# KC_BaseBoard4CompareTest-V0_3.net
KiCad netlist of a schematic drawn in Altium Designer
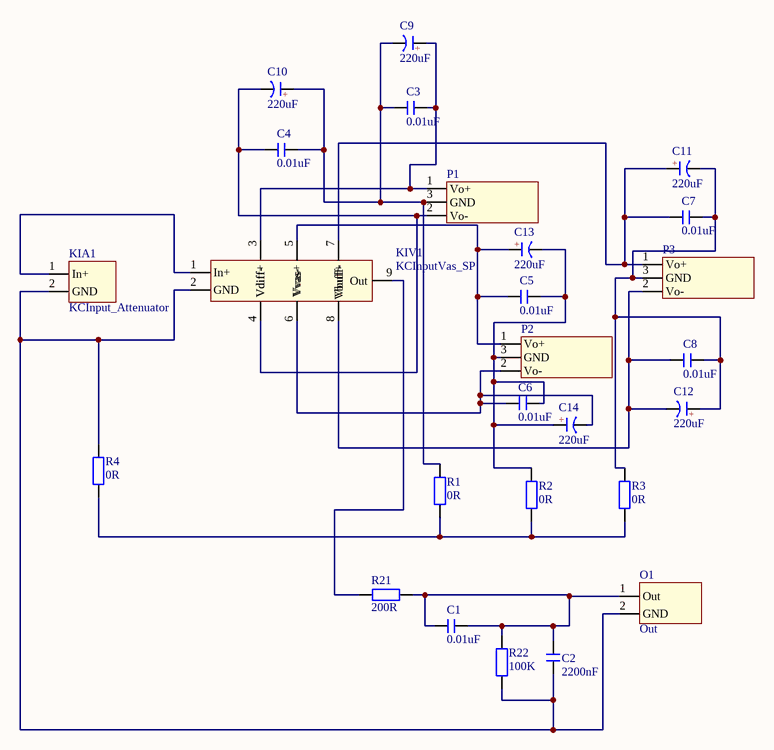
[diagram p0: KC_BaseBoard4CompareTest-V0.3.SchDoc]

(export (version "E")
  (design (tool "Eeschema 10.0.6"))
  (components
    (comp (ref "C1")
      (value "0.01uF")
      (footprint "CBB 6.3*6.3*5")
      (description "CBB电容")
      (fields (field (name "版权归属") "源创客"))
      (libsource (lib "电阻-电容-电感") (part "C-CBB"))
    )
    (comp (ref "C2")
      (value "2200nF")
      (footprint "CBB 6.3*6.3*5")
      (description "CBB电容")
      (fields (field (name "版权归属") "源创客"))
      (libsource (lib "电阻-电容-电感") (part "C-CBB"))
    )
    (comp (ref "C3")
      (value "0.01uF")
      (footprint "CBB 6.3*6.3*5")
      (description "CBB电容")
      (fields (field (name "版权归属") "源创客"))
      (libsource (lib "电阻-电容-电感") (part "C-CBB"))
    )
    (comp (ref "C4")
      (value "0.01uF")
      (footprint "CBB 6.3*6.3*5")
      (description "CBB电容")
      (fields (field (name "版权归属") "源创客"))
      (libsource (lib "电阻-电容-电感") (part "C-CBB"))
    )
    (comp (ref "C5")
      (value "0.01uF")
      (footprint "CBB 6.3*6.3*5")
      (description "CBB电容")
      (fields (field (name "版权归属") "源创客"))
      (libsource (lib "电阻-电容-电感") (part "C-CBB"))
    )
    (comp (ref "C6")
      (value "0.01uF")
      (footprint "CBB 6.3*6.3*5")
      (description "CBB电容")
      (fields (field (name "版权归属") "源创客"))
      (libsource (lib "电阻-电容-电感") (part "C-CBB"))
    )
    (comp (ref "C7")
      (value "0.01uF")
      (footprint "CBB 6.3*6.3*5")
      (description "CBB电容")
      (fields (field (name "版权归属") "源创客"))
      (libsource (lib "电阻-电容-电感") (part "C-CBB"))
    )
    (comp (ref "C8")
      (value "0.01uF")
      (footprint "CBB 6.3*6.3*5")
      (description "CBB电容")
      (fields (field (name "版权归属") "源创客"))
      (libsource (lib "电阻-电容-电感") (part "C-CBB"))
    )
    (comp (ref "C9")
      (value "220uF")
      (footprint "CAP 5.0*10*12.5")
      (description "直插电解电容")
      (fields (field (name "版权归属") "源创客"))
      (libsource (lib "电阻-电容-电感") (part "C-CAP"))
    )
    (comp (ref "C10")
      (value "220uF")
      (footprint "CAP 5.0*10*12.5")
      (description "直插电解电容")
      (fields (field (name "版权归属") "源创客"))
      (libsource (lib "电阻-电容-电感") (part "C-CAP"))
    )
    (comp (ref "C11")
      (value "220uF")
      (footprint "CAP 5.0*10*12.5")
      (description "直插电解电容")
      (fields (field (name "版权归属") "源创客"))
      (libsource (lib "电阻-电容-电感") (part "C-CAP"))
    )
    (comp (ref "C12")
      (value "220uF")
      (footprint "CAP 5.0*10*12.5")
      (description "直插电解电容")
      (fields (field (name "版权归属") "源创客"))
      (libsource (lib "电阻-电容-电感") (part "C-CAP"))
    )
    (comp (ref "C13")
      (value "220uF")
      (footprint "CAP 5.0*10*12.5")
      (description "直插电解电容")
      (fields (field (name "版权归属") "源创客"))
      (libsource (lib "电阻-电容-电感") (part "C-CAP"))
    )
    (comp (ref "C14")
      (value "220uF")
      (footprint "CAP 5.0*10*12.5")
      (description "直插电解电容")
      (fields (field (name "版权归属") "源创客"))
      (libsource (lib "电阻-电容-电感") (part "C-CAP"))
    )
    (comp (ref "KIA1")
      (value "KCInput_Attenuator")
      (footprint "KCIn_Attenuator")
      (description "King Cello Input Attenuator")
      (libsource (lib "KC_amp") (part "KCInput_Attenuator"))
    )
    (comp (ref "KIV1")
      (value "KCInputVas_SP")
      (footprint "KCIn_VAS_SP_M4")
      (description "King Cello Input Stage and VAS for Seperated Power")
      (libsource (lib "KC_amp") (part "KCInputVas_SP"))
    )
    (comp (ref "O1")
      (value "Out")
      (footprint "Signal_Terminal")
      (description "Signal Out")
      (libsource (lib "KC_amp") (part "Signal_Out"))
    )
    (comp (ref "P1")
      (value "Vdiff")
      (footprint "KC_MBPowerReg4Compare")
      (description "King Cello Compare Test Power")
      (libsource (lib "KC_amp") (part "MainBoardPowerRegulator4CompareTest"))
    )
    (comp (ref "P2")
      (value "Vvas")
      (footprint "KC_MBPowerReg4Compare")
      (description "King Cello Compare Test Power")
      (libsource (lib "KC_amp") (part "MainBoardPowerRegulator4CompareTest"))
    )
    (comp (ref "P3")
      (value "Vbuff")
      (footprint "KC_MBPowerReg4Compare")
      (description "King Cello Compare Test Power")
      (libsource (lib "KC_amp") (part "MainBoardPowerRegulator4CompareTest"))
    )
    (comp (ref "R1")
      (value "0R")
      (footprint "RS 1/4W")
      (description "直插色环电阻")
      (fields (field (name "版权归属") "源创客"))
      (libsource (lib "电阻-电容-电感") (part "R-CRR"))
    )
    (comp (ref "R2")
      (value "0R")
      (footprint "RS 1/4W")
      (description "直插色环电阻")
      (fields (field (name "版权归属") "源创客"))
      (libsource (lib "电阻-电容-电感") (part "R-CRR"))
    )
    (comp (ref "R3")
      (value "0R")
      (footprint "RS 1/4W")
      (description "直插色环电阻")
      (fields (field (name "版权归属") "源创客"))
      (libsource (lib "电阻-电容-电感") (part "R-CRR"))
    )
    (comp (ref "R4")
      (value "0R")
      (footprint "RS 1/4W")
      (description "直插色环电阻")
      (fields (field (name "版权归属") "源创客"))
      (libsource (lib "电阻-电容-电感") (part "R-CRR"))
    )
    (comp (ref "R21")
      (value "200R")
      (footprint "RS 1/4W")
      (description "直插色环电阻")
      (fields (field (name "版权归属") "源创客"))
      (libsource (lib "电阻-电容-电感") (part "R-CRR"))
    )
    (comp (ref "R22")
      (value "100K")
      (footprint "RS 1/4W")
      (description "直插色环电阻")
      (fields (field (name "版权归属") "源创客"))
      (libsource (lib "电阻-电容-电感") (part "R-CRR"))
    )
  )
  (nets
    (net (code "1") (name "Net-(C9-A)") (class "Default")
      (node (ref "C3") (pin "2") (pinfunction "2_2") (pintype "passive"))
      (node (ref "C9") (pin "1") (pinfunction "A_1") (pintype "passive"))
      (node (ref "KIV1") (pin "3") (pinfunction "Vdiff+_3") (pintype "passive"))
      (node (ref "P1") (pin "1") (pinfunction "Vo+_1") (pintype "passive"))
    )
    (net (code "2") (name "Net-(C10-A)") (class "Default")
      (node (ref "C10") (pin "1") (pinfunction "A_1") (pintype "passive"))
      (node (ref "C3") (pin "1") (pinfunction "1_1") (pintype "passive"))
      (node (ref "C4") (pin "2") (pinfunction "2_2") (pintype "passive"))
      (node (ref "C9") (pin "2") (pinfunction "K_2") (pintype "passive"))
      (node (ref "P1") (pin "3") (pinfunction "GND_3") (pintype "passive"))
      (node (ref "R1") (pin "2") (pinfunction "2_2") (pintype "passive"))
    )
    (net (code "3") (name "Net-(C10-K)") (class "Default")
      (node (ref "C10") (pin "2") (pinfunction "K_2") (pintype "passive"))
      (node (ref "C4") (pin "1") (pinfunction "1_1") (pintype "passive"))
      (node (ref "KIV1") (pin "4") (pinfunction "Vdiff-_4") (pintype "passive"))
      (node (ref "P1") (pin "2") (pinfunction "Vo-_2") (pintype "passive"))
    )
    (net (code "4") (name "Net-(C11-A)") (class "Default")
      (node (ref "C11") (pin "1") (pinfunction "A_1") (pintype "passive"))
      (node (ref "C7") (pin "1") (pinfunction "1_1") (pintype "passive"))
      (node (ref "KIV1") (pin "7") (pinfunction "Vbuff+_7") (pintype "passive"))
      (node (ref "P3") (pin "1") (pinfunction "Vo+_1") (pintype "passive"))
    )
    (net (code "5") (name "Net-(C11-K)") (class "Default")
      (node (ref "C11") (pin "2") (pinfunction "K_2") (pintype "passive"))
      (node (ref "C12") (pin "1") (pinfunction "A_1") (pintype "passive"))
      (node (ref "C7") (pin "2") (pinfunction "2_2") (pintype "passive"))
      (node (ref "C8") (pin "2") (pinfunction "2_2") (pintype "passive"))
      (node (ref "P3") (pin "3") (pinfunction "GND_3") (pintype "passive"))
      (node (ref "R3") (pin "2") (pinfunction "2_2") (pintype "passive"))
    )
    (net (code "6") (name "Net-(C12-K)") (class "Default")
      (node (ref "C12") (pin "2") (pinfunction "K_2") (pintype "passive"))
      (node (ref "C8") (pin "1") (pinfunction "1_1") (pintype "passive"))
      (node (ref "KIV1") (pin "8") (pinfunction "Vbuff-_8") (pintype "passive"))
      (node (ref "P3") (pin "2") (pinfunction "Vo-_2") (pintype "passive"))
    )
    (net (code "7") (name "Net-(C13-A)") (class "Default")
      (node (ref "C13") (pin "1") (pinfunction "A_1") (pintype "passive"))
      (node (ref "C5") (pin "1") (pinfunction "1_1") (pintype "passive"))
      (node (ref "KIV1") (pin "5") (pinfunction "Vvas+_5") (pintype "passive"))
      (node (ref "P2") (pin "1") (pinfunction "Vo+_1") (pintype "passive"))
    )
    (net (code "8") (name "Net-(C13-K)") (class "Default")
      (node (ref "C13") (pin "2") (pinfunction "K_2") (pintype "passive"))
      (node (ref "C14") (pin "1") (pinfunction "A_1") (pintype "passive"))
      (node (ref "C5") (pin "2") (pinfunction "2_2") (pintype "passive"))
      (node (ref "C6") (pin "2") (pinfunction "2_2") (pintype "passive"))
      (node (ref "P2") (pin "3") (pinfunction "GND_3") (pintype "passive"))
      (node (ref "R2") (pin "2") (pinfunction "2_2") (pintype "passive"))
    )
    (net (code "9") (name "Net-(C14-K)") (class "Default")
      (node (ref "C14") (pin "2") (pinfunction "K_2") (pintype "passive"))
      (node (ref "C6") (pin "1") (pinfunction "1_1") (pintype "passive"))
      (node (ref "KIV1") (pin "6") (pinfunction "Vvas-_6") (pintype "passive"))
      (node (ref "P2") (pin "2") (pinfunction "Vo-_2") (pintype "passive"))
    )
    (net (code "10") (name "Net-(KIA1-GND)") (class "Default")
      (node (ref "C2") (pin "2") (pinfunction "2_2") (pintype "passive"))
      (node (ref "KIA1") (pin "2") (pinfunction "GND_2") (pintype "passive"))
      (node (ref "KIV1") (pin "2") (pinfunction "GND_2") (pintype "passive"))
      (node (ref "O1") (pin "2") (pinfunction "GND_2") (pintype "passive"))
      (node (ref "R22") (pin "2") (pinfunction "2_2") (pintype "passive"))
      (node (ref "R4") (pin "2") (pinfunction "2_2") (pintype "passive"))
    )
    (net (code "11") (name "Net-(KIA1-In+)") (class "Default")
      (node (ref "KIA1") (pin "1") (pinfunction "In+_1") (pintype "passive"))
      (node (ref "KIV1") (pin "1") (pinfunction "In+_1") (pintype "passive"))
    )
    (net (code "12") (name "Net-(KIV1-Out)") (class "Default")
      (node (ref "KIV1") (pin "9") (pinfunction "Out_9") (pintype "passive"))
      (node (ref "R21") (pin "2") (pinfunction "2_2") (pintype "passive"))
    )
    (net (code "13") (name "Net-(O1-Out)") (class "Default")
      (node (ref "C1") (pin "1") (pinfunction "1_1") (pintype "passive"))
      (node (ref "C1") (pin "2") (pinfunction "2_2") (pintype "passive"))
      (node (ref "C2") (pin "1") (pinfunction "1_1") (pintype "passive"))
      (node (ref "O1") (pin "1") (pinfunction "Out_1") (pintype "passive"))
      (node (ref "R21") (pin "1") (pinfunction "1_1") (pintype "passive"))
      (node (ref "R22") (pin "1") (pinfunction "1_1") (pintype "passive"))
    )
    (net (code "14") (name "Net-(R1-Pad1)") (class "Default")
      (node (ref "R1") (pin "1") (pinfunction "1_1") (pintype "passive"))
      (node (ref "R2") (pin "1") (pinfunction "1_1") (pintype "passive"))
      (node (ref "R3") (pin "1") (pinfunction "1_1") (pintype "passive"))
      (node (ref "R4") (pin "1") (pinfunction "1_1") (pintype "passive"))
    )
  )
)
